# PCB_BALISE_328P.net
KiCad netlist of a schematic drawn in EAGLE
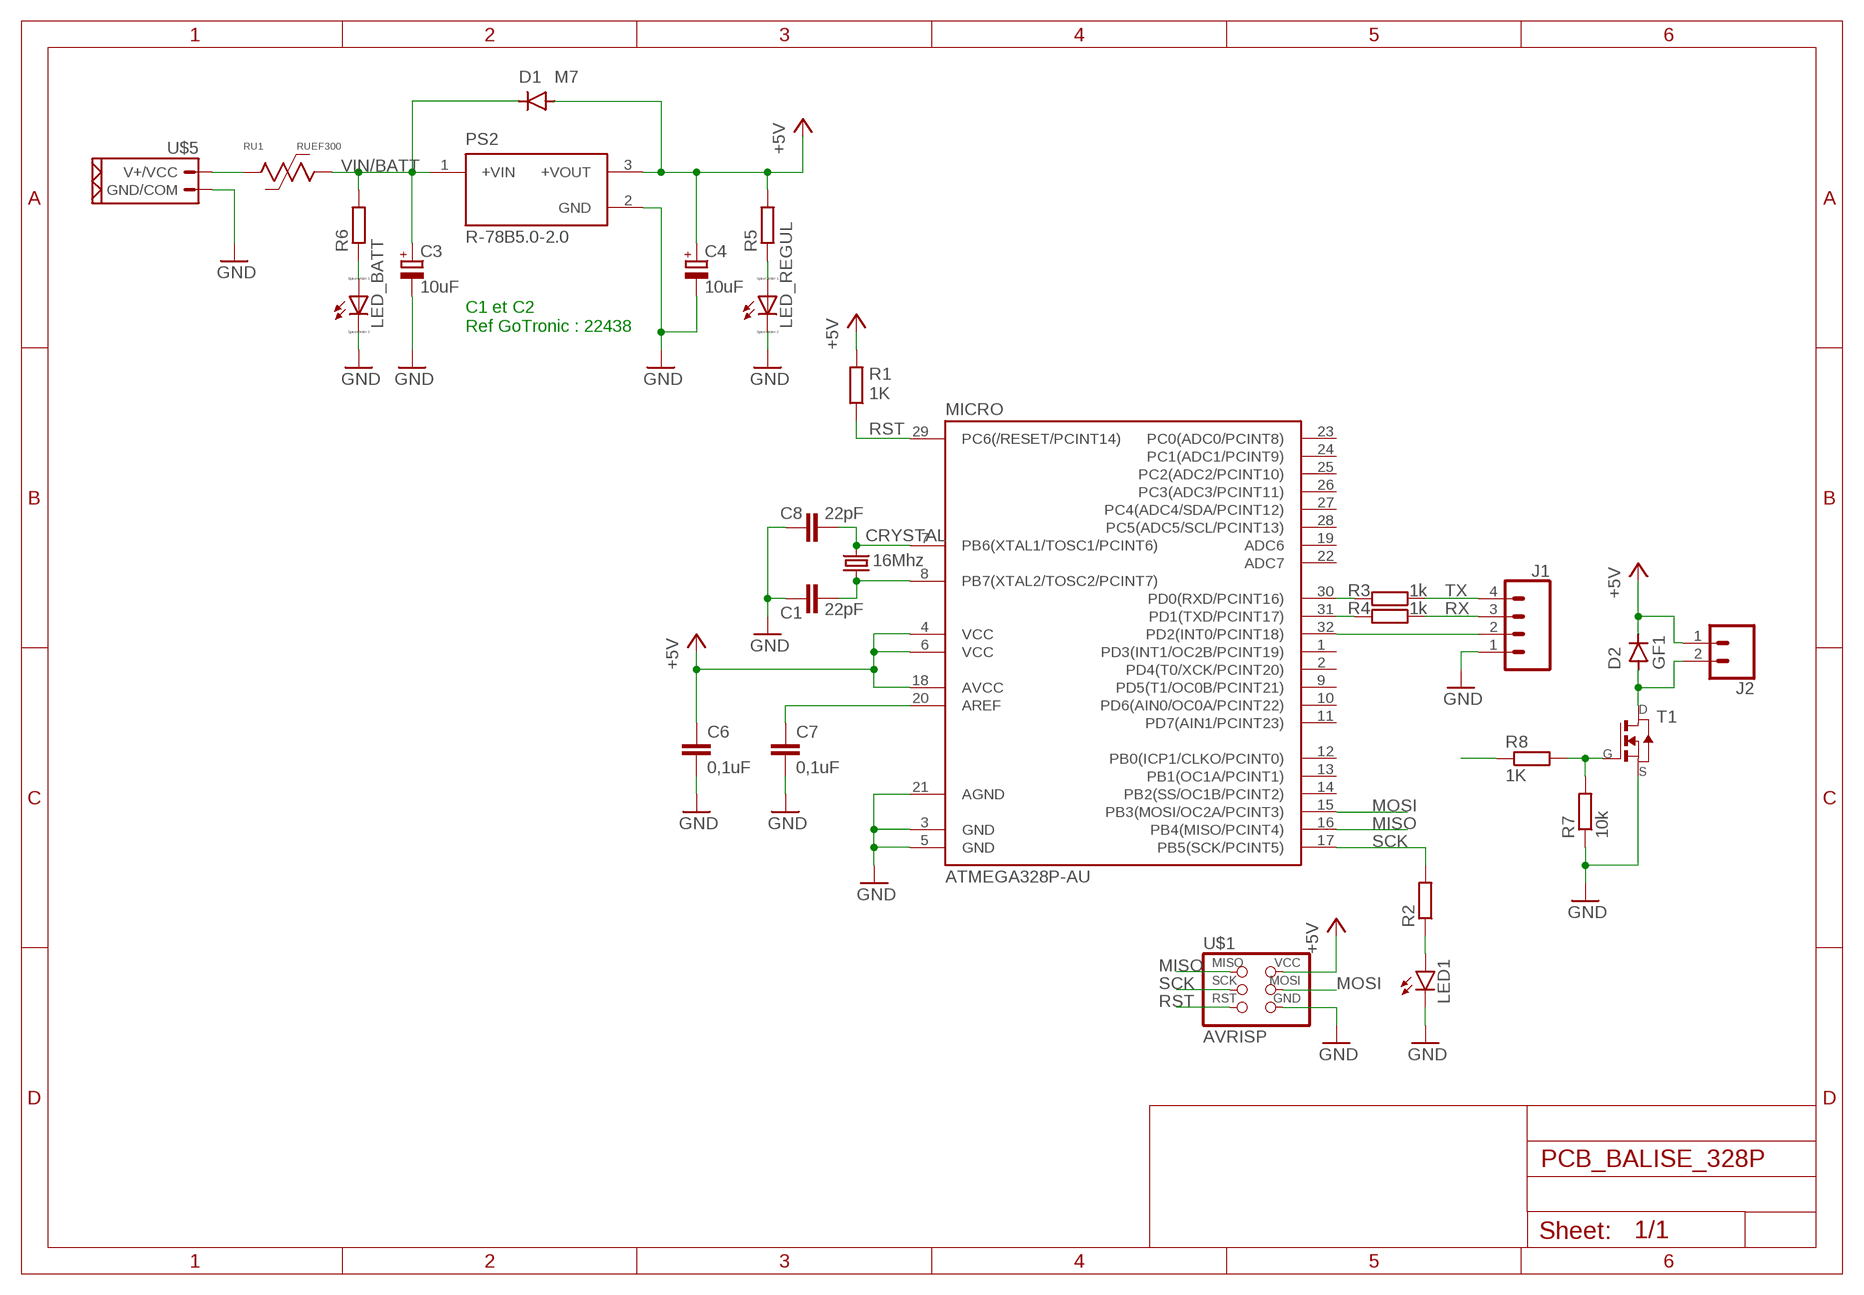
[diagram p0: schematic, sheet 1]

(export (version "E")
  (design (tool "Eeschema 10.0.6"))
  (components
    (comp (ref "C1")
      (value "22pF")
      (footprint "eagle-import:C1206K")
      (libsource (lib "eagle-import") (part "C-EUC1206K"))
    )
    (comp (ref "C3")
      (value "10uF")
      (footprint "eagle-import:153CLV-0505")
      (libsource (lib "eagle-import") (part "CPOL-EU153CLV-0505"))
    )
    (comp (ref "C4")
      (value "10uF")
      (footprint "eagle-import:153CLV-0505")
      (libsource (lib "eagle-import") (part "CPOL-EU153CLV-0505"))
    )
    (comp (ref "C6")
      (value "0,1uF")
      (footprint "eagle-import:C1206K")
      (libsource (lib "eagle-import") (part "C-EUC1206K"))
    )
    (comp (ref "C7")
      (value "0,1uF")
      (footprint "eagle-import:C1206K")
      (libsource (lib "eagle-import") (part "C-EUC1206K"))
    )
    (comp (ref "C8")
      (value "22pF")
      (footprint "eagle-import:C1206K")
      (libsource (lib "eagle-import") (part "C-EUC1206K"))
    )
    (comp (ref "CRYSTAL")
      (value "16Mhz")
      (footprint "eagle-import:CSM-7X-DU")
      (libsource (lib "eagle-import") (part "CSM-7X-DU"))
    )
    (comp (ref "D1")
      (value "M7")
      (footprint "eagle-import:MINI-SMA")
      (libsource (lib "eagle-import") (part "CDBM1100-G"))
    )
    (comp (ref "D2")
      (value "GF1")
      (footprint "eagle-import:SMA-DO214AC")
      (libsource (lib "eagle-import") (part "GF1"))
    )
    (comp (ref "J1")
      (value "CONN_04POLAR")
      (footprint "eagle-import:MOLEX-1X4")
      (libsource (lib "eagle-import") (part "CONN_04POLAR"))
    )
    (comp (ref "J2")
      (value "CONN_02POLAR")
      (footprint "eagle-import:MOLEX-1X2")
      (libsource (lib "eagle-import") (part "CONN_02POLAR"))
    )
    (comp (ref "LED1")
      (value "LEDSMT1206")
      (footprint "eagle-import:1206")
      (libsource (lib "eagle-import") (part "LEDSMT1206"))
    )
    (comp (ref "LED_BATT")
      (value "LED_E")
      (footprint "eagle-import:LED_1206")
      (libsource (lib "eagle-import") (part "LED_E"))
    )
    (comp (ref "LED_REGUL")
      (value "LED_E")
      (footprint "eagle-import:LED_1206")
      (libsource (lib "eagle-import") (part "LED_E"))
    )
    (comp (ref "MICRO")
      (value "ATMEGA328P-AU")
      (footprint "eagle-import:TQFP32-08")
      (libsource (lib "eagle-import") (part "ATMEGA48/88/168-AU"))
    )
    (comp (ref "PS2")
      (value "R-78B5.0-2.0")
      (footprint "eagle-import:CONV_R-78B5.0-2.0")
      (fields (field (name "MF") "Recom Power"))
      (libsource (lib "eagle-import") (part "R-78B5.0-2.0"))
    )
    (comp (ref "R1")
      (value "1K")
      (footprint "eagle-import:R1206")
      (libsource (lib "eagle-import") (part "R-EU_R1206"))
    )
    (comp (ref "R2")
      (value "R-EU_R1206")
      (footprint "eagle-import:R1206")
      (libsource (lib "eagle-import") (part "R-EU_R1206"))
    )
    (comp (ref "R3")
      (value "1k")
      (footprint "eagle-import:R1206")
      (libsource (lib "eagle-import") (part "R-EU_R1206"))
    )
    (comp (ref "R4")
      (value "1k")
      (footprint "eagle-import:R1206")
      (libsource (lib "eagle-import") (part "R-EU_R1206"))
    )
    (comp (ref "R5")
      (value "R-EU_R1206")
      (footprint "eagle-import:R1206")
      (libsource (lib "eagle-import") (part "R-EU_R1206"))
    )
    (comp (ref "R6")
      (value "R-EU_R1206")
      (footprint "eagle-import:R1206")
      (libsource (lib "eagle-import") (part "R-EU_R1206"))
    )
    (comp (ref "R7")
      (value "10k")
      (footprint "eagle-import:R1206")
      (libsource (lib "eagle-import") (part "R-EU_R1206"))
    )
    (comp (ref "R8")
      (value "1K")
      (footprint "eagle-import:R1206")
      (libsource (lib "eagle-import") (part "R-EU_R1206"))
    )
    (comp (ref "RU1")
      (value "RUEF300")
      (footprint "eagle-import:RUEF300")
      (libsource (lib "eagle-import") (part "RUEF300"))
    )
    (comp (ref "T1")
      (value "NMOSFETSOT23")
      (footprint "eagle-import:SOT-23")
      (libsource (lib "eagle-import") (part "NMOSFETSOT23"))
    )
    (comp (ref "U$1")
      (value "AVRISP")
      (footprint "eagle-import:2X03")
      (libsource (lib "eagle-import") (part "AVRISP"))
    )
    (comp (ref "U$5")
      (value "CONN_02_PUIXT30")
      (footprint "eagle-import:XT30_FEMALE")
      (libsource (lib "eagle-import") (part "CONN_02_PUIXT30"))
    )
  )
  (nets
    (net (code "1") (name "+5V") (class "Default")
      (node (ref "C4") (pin "+") (pinfunction "+_+") (pintype "passive"))
      (node (ref "C6") (pin "1") (pinfunction "1_1") (pintype "passive"))
      (node (ref "D1") (pin "ANODE") (pinfunction "ANODE_ANODE") (pintype "bidirectional"))
      (node (ref "D2") (pin "K") (pinfunction "C_K") (pintype "passive"))
      (node (ref "J2") (pin "1") (pinfunction "1_1") (pintype "passive"))
      (node (ref "MICRO") (pin "18") (pinfunction "AVCC_18") (pintype "passive"))
      (node (ref "MICRO") (pin "4") (pinfunction "VCC_4") (pintype "power_in"))
      (node (ref "MICRO") (pin "6") (pinfunction "VCC_6") (pintype "power_in"))
      (node (ref "PS2") (pin "3") (pinfunction "+VOUT_3") (pintype "output"))
      (node (ref "R1") (pin "2") (pinfunction "2_2") (pintype "passive"))
      (node (ref "R5") (pin "2") (pinfunction "2_2") (pintype "passive"))
      (node (ref "U$1") (pin "2") (pinfunction "VCC_2") (pintype "passive"))
    )
    (net (code "2") (name "/MISO") (class "Default")
      (node (ref "MICRO") (pin "16") (pinfunction "PB4(MISO/PCINT4)_16") (pintype "bidirectional"))
      (node (ref "U$1") (pin "1") (pinfunction "MISO_1") (pintype "passive"))
    )
    (net (code "3") (name "/MOSI") (class "Default")
      (node (ref "MICRO") (pin "15") (pinfunction "PB3(MOSI/OC2A/PCINT3)_15") (pintype "bidirectional"))
      (node (ref "U$1") (pin "4") (pinfunction "MOSI_4") (pintype "passive"))
    )
    (net (code "4") (name "/RST") (class "Default")
      (node (ref "MICRO") (pin "29") (pinfunction "PC6(/RESET/PCINT14)_29") (pintype "bidirectional"))
      (node (ref "R1") (pin "1") (pinfunction "1_1") (pintype "passive"))
      (node (ref "U$1") (pin "5") (pinfunction "RST_5") (pintype "passive"))
    )
    (net (code "5") (name "/RX") (class "Default")
      (node (ref "J1") (pin "3") (pinfunction "3_3") (pintype "passive"))
      (node (ref "R4") (pin "1") (pinfunction "1_1") (pintype "passive"))
    )
    (net (code "6") (name "/SCK") (class "Default")
      (node (ref "MICRO") (pin "17") (pinfunction "PB5(SCK/PCINT5)_17") (pintype "bidirectional"))
      (node (ref "R2") (pin "2") (pinfunction "2_2") (pintype "passive"))
      (node (ref "U$1") (pin "3") (pinfunction "SCK_3") (pintype "passive"))
    )
    (net (code "7") (name "/TX") (class "Default")
      (node (ref "J1") (pin "4") (pinfunction "4_4") (pintype "passive"))
      (node (ref "R3") (pin "1") (pinfunction "1_1") (pintype "passive"))
    )
    (net (code "8") (name "/VIN{slash}BATT") (class "Default")
      (node (ref "C3") (pin "+") (pinfunction "+_+") (pintype "passive"))
      (node (ref "D1") (pin "KATHODE") (pinfunction "KATHODE_KATHODE") (pintype "bidirectional"))
      (node (ref "PS2") (pin "1") (pinfunction "+VIN_1") (pintype "input"))
      (node (ref "R6") (pin "2") (pinfunction "2_2") (pintype "passive"))
      (node (ref "RU1") (pin "P$2") (pinfunction "P$2_P$2") (pintype "passive"))
    )
    (net (code "9") (name "GND") (class "Default")
      (node (ref "C1") (pin "1") (pinfunction "1_1") (pintype "passive"))
      (node (ref "C3") (pin "-") (pinfunction "-_-") (pintype "passive"))
      (node (ref "C4") (pin "-") (pinfunction "-_-") (pintype "passive"))
      (node (ref "C6") (pin "2") (pinfunction "2_2") (pintype "passive"))
      (node (ref "C7") (pin "2") (pinfunction "2_2") (pintype "passive"))
      (node (ref "C8") (pin "1") (pinfunction "1_1") (pintype "passive"))
      (node (ref "J1") (pin "1") (pinfunction "1_1") (pintype "passive"))
      (node (ref "LED1") (pin "C") (pinfunction "C_C") (pintype "passive"))
      (node (ref "LED_BATT") (pin "C") (pinfunction "C_C") (pintype "passive"))
      (node (ref "LED_REGUL") (pin "C") (pinfunction "C_C") (pintype "passive"))
      (node (ref "MICRO") (pin "21") (pinfunction "AGND_21") (pintype "power_in"))
      (node (ref "MICRO") (pin "3") (pinfunction "GND_3") (pintype "power_in"))
      (node (ref "MICRO") (pin "5") (pinfunction "GND_5") (pintype "power_in"))
      (node (ref "PS2") (pin "2") (pinfunction "GND_2") (pintype "power_in"))
      (node (ref "R7") (pin "1") (pinfunction "1_1") (pintype "passive"))
      (node (ref "T1") (pin "2") (pinfunction "S_2") (pintype "passive"))
      (node (ref "U$1") (pin "6") (pinfunction "GND_6") (pintype "passive"))
      (node (ref "U$5") (pin "P$2") (pinfunction "GND/COM_P$2") (pintype "passive"))
    )
    (net (code "10") (name "Net-(LED1-PadA)") (class "Default")
      (node (ref "LED1") (pin "A") (pinfunction "A_A") (pintype "passive"))
      (node (ref "R2") (pin "1") (pinfunction "1_1") (pintype "passive"))
    )
    (net (code "11") (name "Net-(LED_BATT-PadA)") (class "Default")
      (node (ref "LED_BATT") (pin "A") (pinfunction "A_A") (pintype "passive"))
      (node (ref "R6") (pin "1") (pinfunction "1_1") (pintype "passive"))
    )
    (net (code "12") (name "Net-(LED_REGUL-PadA)") (class "Default")
      (node (ref "LED_REGUL") (pin "A") (pinfunction "A_A") (pintype "passive"))
      (node (ref "R5") (pin "1") (pinfunction "1_1") (pintype "passive"))
    )
    (net (code "13") (name "Net-(MICRO-AREF)") (class "Default")
      (node (ref "C7") (pin "1") (pinfunction "1_1") (pintype "passive"))
      (node (ref "MICRO") (pin "20") (pinfunction "AREF_20") (pintype "passive"))
    )
    (net (code "14") (name "Net-(MICRO-PB6(XTAL1{slash}TOSC1{slash}PCINT6))") (class "Default")
      (node (ref "C8") (pin "2") (pinfunction "2_2") (pintype "passive"))
      (node (ref "CRYSTAL") (pin "2") (pinfunction "2_2") (pintype "passive"))
      (node (ref "MICRO") (pin "7") (pinfunction "PB6(XTAL1/TOSC1/PCINT6)_7") (pintype "bidirectional"))
    )
    (net (code "15") (name "Net-(MICRO-PB7(XTAL2{slash}TOSC2{slash}PCINT7))") (class "Default")
      (node (ref "C1") (pin "2") (pinfunction "2_2") (pintype "passive"))
      (node (ref "CRYSTAL") (pin "1") (pinfunction "1_1") (pintype "passive"))
      (node (ref "MICRO") (pin "8") (pinfunction "PB7(XTAL2/TOSC2/PCINT7)_8") (pintype "bidirectional"))
    )
    (net (code "16") (name "Net-(MICRO-PD0(RXD{slash}PCINT16))") (class "Default")
      (node (ref "MICRO") (pin "30") (pinfunction "PD0(RXD/PCINT16)_30") (pintype "bidirectional"))
      (node (ref "R3") (pin "2") (pinfunction "2_2") (pintype "passive"))
    )
    (net (code "17") (name "Net-(MICRO-PD1(TXD{slash}PCINT17))") (class "Default")
      (node (ref "MICRO") (pin "31") (pinfunction "PD1(TXD/PCINT17)_31") (pintype "bidirectional"))
      (node (ref "R4") (pin "2") (pinfunction "2_2") (pintype "passive"))
    )
    (net (code "18") (name "Net-(MICRO-PD2(INT0{slash}PCINT18))") (class "Default")
      (node (ref "J1") (pin "2") (pinfunction "2_2") (pintype "passive"))
      (node (ref "MICRO") (pin "32") (pinfunction "PD2(INT0/PCINT18)_32") (pintype "bidirectional"))
    )
    (net (code "19") (name "Net-(T1-D)") (class "Default")
      (node (ref "D2") (pin "A") (pinfunction "A_A") (pintype "passive"))
      (node (ref "J2") (pin "2") (pinfunction "2_2") (pintype "passive"))
      (node (ref "T1") (pin "1") (pinfunction "D_1") (pintype "passive"))
    )
    (net (code "20") (name "Net-(T1-G)") (class "Default")
      (node (ref "R7") (pin "2") (pinfunction "2_2") (pintype "passive"))
      (node (ref "R8") (pin "2") (pinfunction "2_2") (pintype "passive"))
      (node (ref "T1") (pin "3") (pinfunction "G_3") (pintype "passive"))
    )
    (net (code "21") (name "Net-(U$5-V+{slash}VCC)") (class "Default")
      (node (ref "RU1") (pin "P$1") (pinfunction "P$1_P$1") (pintype "passive"))
      (node (ref "U$5") (pin "P$1") (pinfunction "V+/VCC_P$1") (pintype "passive"))
    )
    (net (code "22") (name "unconnected-(MICRO-ADC6-Pad19)") (class "Default")
      (node (ref "MICRO") (pin "19") (pinfunction "ADC6_19") (pintype "passive"))
    )
    (net (code "23") (name "unconnected-(MICRO-ADC7-Pad22)") (class "Default")
      (node (ref "MICRO") (pin "22") (pinfunction "ADC7_22") (pintype "passive"))
    )
    (net (code "24") (name "unconnected-(MICRO-PB0(ICP1{slash}CLKO{slash}PCINT0)-Pad12)") (class "Default")
      (node (ref "MICRO") (pin "12") (pinfunction "PB0(ICP1/CLKO/PCINT0)_12") (pintype "bidirectional"))
    )
    (net (code "25") (name "unconnected-(MICRO-PB1(OC1A{slash}PCINT1)-Pad13)") (class "Default")
      (node (ref "MICRO") (pin "13") (pinfunction "PB1(OC1A/PCINT1)_13") (pintype "bidirectional"))
    )
    (net (code "26") (name "unconnected-(MICRO-PB2(SS{slash}OC1B{slash}PCINT2)-Pad14)") (class "Default")
      (node (ref "MICRO") (pin "14") (pinfunction "PB2(SS/OC1B/PCINT2)_14") (pintype "bidirectional"))
    )
    (net (code "27") (name "unconnected-(MICRO-PC0(ADC0{slash}PCINT8)-Pad23)") (class "Default")
      (node (ref "MICRO") (pin "23") (pinfunction "PC0(ADC0/PCINT8)_23") (pintype "bidirectional"))
    )
    (net (code "28") (name "unconnected-(MICRO-PC1(ADC1{slash}PCINT9)-Pad24)") (class "Default")
      (node (ref "MICRO") (pin "24") (pinfunction "PC1(ADC1/PCINT9)_24") (pintype "bidirectional"))
    )
    (net (code "29") (name "unconnected-(MICRO-PC2(ADC2{slash}PCINT10)-Pad25)") (class "Default")
      (node (ref "MICRO") (pin "25") (pinfunction "PC2(ADC2/PCINT10)_25") (pintype "bidirectional"))
    )
    (net (code "30") (name "unconnected-(MICRO-PC3(ADC3{slash}PCINT11)-Pad26)") (class "Default")
      (node (ref "MICRO") (pin "26") (pinfunction "PC3(ADC3/PCINT11)_26") (pintype "bidirectional"))
    )
    (net (code "31") (name "unconnected-(MICRO-PC4(ADC4{slash}SDA{slash}PCINT12)-Pad27)") (class "Default")
      (node (ref "MICRO") (pin "27") (pinfunction "PC4(ADC4/SDA/PCINT12)_27") (pintype "bidirectional"))
    )
    (net (code "32") (name "unconnected-(MICRO-PC5(ADC5{slash}SCL{slash}PCINT13)-Pad28)") (class "Default")
      (node (ref "MICRO") (pin "28") (pinfunction "PC5(ADC5/SCL/PCINT13)_28") (pintype "bidirectional"))
    )
    (net (code "33") (name "unconnected-(MICRO-PD3(INT1{slash}OC2B{slash}PCINT19)-Pad1)") (class "Default")
      (node (ref "MICRO") (pin "1") (pinfunction "PD3(INT1/OC2B/PCINT19)_1") (pintype "bidirectional"))
    )
    (net (code "34") (name "unconnected-(MICRO-PD4(T0{slash}XCK{slash}PCINT20)-Pad2)") (class "Default")
      (node (ref "MICRO") (pin "2") (pinfunction "PD4(T0/XCK/PCINT20)_2") (pintype "bidirectional"))
    )
    (net (code "35") (name "unconnected-(MICRO-PD5(T1{slash}OC0B{slash}PCINT21)-Pad9)") (class "Default")
      (node (ref "MICRO") (pin "9") (pinfunction "PD5(T1/OC0B/PCINT21)_9") (pintype "bidirectional"))
    )
    (net (code "36") (name "unconnected-(MICRO-PD6(AIN0{slash}OC0A{slash}PCINT22)-Pad10)") (class "Default")
      (node (ref "MICRO") (pin "10") (pinfunction "PD6(AIN0/OC0A/PCINT22)_10") (pintype "bidirectional"))
    )
    (net (code "37") (name "unconnected-(MICRO-PD7(AIN1{slash}PCINT23)-Pad11)") (class "Default")
      (node (ref "MICRO") (pin "11") (pinfunction "PD7(AIN1/PCINT23)_11") (pintype "bidirectional"))
    )
    (net (code "38") (name "unconnected-(R8-Pad1)") (class "Default")
      (node (ref "R8") (pin "1") (pinfunction "1_1") (pintype "passive"))
    )
  )
)
